# LM2596.net
KiCad netlist of a schematic drawn in Altium Designer
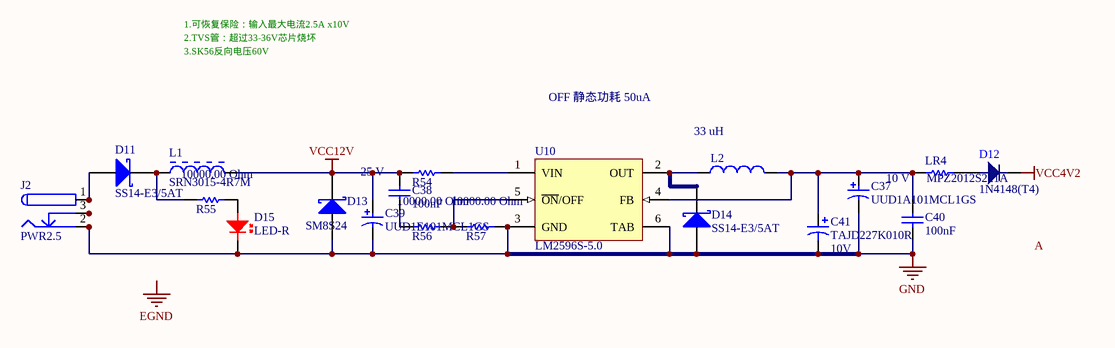
[diagram p0: LM2596.SchDoc]

(export (version "E")
  (design (tool "Eeschema 10.0.6"))
  (components
    (comp (ref "C37")
      (value "UUD1A101MCL1GS")
      (footprint "NIC-CAPA2-6.3X5.8_V")
      (fields (field (name "RATED VOLTAGE") "10 V") (field (name "MANUFACTURER") "Nichicon"))
      (libsource (lib "Altium Content Vault") (part "CMP-0687-00054-1"))
    )
    (comp (ref "C38")
      (value "100nF")
      (footprint "CAPC0805(2012)100_L")
      (description "CAP 100nF 50V ±5% 0805 (2012 Metric) Thickness 1mm SMD")
      (fields (field (name "TOLERANCE") "±5%") (field (name "Comment") "CAP 100nF 50V 0805(2012)"))
      (libsource (lib "Altium Content Vault") (part "CMP-1036-04418-1"))
    )
    (comp (ref "C39")
      (value "UUD1E101MCL1GS")
      (footprint "NIC-CAPA2-6.3X7.7_V")
      (fields (field (name "RATED VOLTAGE") "25 V") (field (name "MANUFACTURER") "Nichicon"))
      (libsource (lib "Altium Content Vault") (part "CMP-0687-00063-1"))
    )
    (comp (ref "C40")
      (value "100nF")
      (footprint "CAPC0805(2012)100_L")
      (description "CAP 100nF 50V ±5% 0805 (2012 Metric) Thickness 1mm SMD")
      (fields (field (name "TOLERANCE") "±5%") (field (name "Comment") "CAP 100nF 50V 0805(2012)"))
      (libsource (lib "Altium Content Vault") (part "CMP-1036-04418-1"))
    )
    (comp (ref "C41")
      (value "TAJD227K010R")
      (footprint "AVX-CAPC7343_V")
      (description "Capacitor, Tantalum, 220uF 10% 10V MCCT-D (7343-31)")
      (fields
        (field (name "MANUFACTURER") "AVX")
        (field (name "TOLERANCE") "10%")
        (field (name "RATED VOLTAGE") "10V")
      )
      (libsource (lib "Altium Content Vault") (part "CMP-0279-00002-1"))
    )
    (comp (ref "D11")
      (value "SS14-E3/5AT")
      (footprint "VISH-DO-214AC-2_V")
      (fields (field (name "MANUFACTURER") "Vishay Semiconductor"))
      (libsource (lib "Altium Content Vault") (part "VISH-DSKY_A1K2-2"))
    )
    (comp (ref "D12")
      (value "1N4148(T4)")
      (footprint "SOD-123")
      (description "高速开关二极管")
      (libsource (lib "mylib") (part "1N4148"))
    )
    (comp (ref "D13")
      (value "SM8S24")
      (footprint "Miscellaneous Devices:DIODE_SMC")
      (description "TVS")
      (libsource (lib "IR Rectifier - Schottky") (part "30BQ040"))
    )
    (comp (ref "D14")
      (value "SS14-E3/5AT")
      (footprint "VISH-DO-214AC-2_V")
      (fields (field (name "MANUFACTURER") "Vishay Semiconductor"))
      (libsource (lib "Altium Content Vault") (part "VISH-DSKY_A1K2-2"))
    )
    (comp (ref "D15")
      (value "LED-R")
      (footprint "DIO-LIG")
      (description "红色LED")
      (libsource (lib "mylib") (part "LED-RED"))
    )
    (comp (ref "J2")
      (value "PWR2.5")
      (footprint "KLD-0202")
      (description "Low Voltage Power Supply Connector")
      (fields (field (name "PUBLISHER") "Altium Limited"))
      (libsource (lib "Miscellaneous Connectors") (part "PWR2.5"))
    )
    (comp (ref "L1")
      (value "SRN3015-4R7M")
      (footprint "BOUR-SRN3015-2_V")
      (fields (field (name "MANUFACTURER") "Bourns"))
      (libsource (lib "Altium Content Vault") (part "BOUR-IND-2A"))
    )
    (comp (ref "L2")
      (value "SLF7045T-330M1R1-H")
      (footprint "INDP5050X28N")
      (description "固定电感器 SMD Power Inductor")
      (fields
        (field (name "MANUFACTURER") "TDK")
        (field (name "INDUCTANCE") "33 uH")
        (field (name "TOLERANCE") "20 %")
      )
      (libsource (lib "Miscellaneous Devices") (part "Inductor"))
    )
    (comp (ref "LR4")
      (value "MPZ2012S221A")
      (footprint "2012[0805]")
      (description "电磁干扰滤波珠子、扼流圈和阵列 Ferrite Chip Beads")
      (fields (field (name "MANUFACTURER") "TDK"))
      (libsource (lib "Miscellaneous Devices") (part "Res Semi"))
    )
    (comp (ref "R54")
      (value "2R 1% 0805(2012)")
      (footprint "RESC0805(2012)_L")
      (description "2R 0.125W 1% 0805 (2012 Metric)  SMD")
      (fields (field (name "TOLERANCE") "1 %") (field (name "POWER") "0.125 W"))
      (libsource (lib "Altium Content Vault") (part "RES"))
    )
    (comp (ref "R55")
      (value "10000.00 Ohm")
      (footprint "RESC0805(2012)_M")
      (description "10K 0.125W 1% 0805 (2012 Metric)  SMD")
      (fields (field (name "TOLERANCE") "1 %") (field (name "POWER") "0.125 W"))
      (libsource (lib "Altium Content Vault") (part "CMP-1013-00623-1"))
    )
    (comp (ref "R56")
      (value "10000.00 Ohm")
      (footprint "RESC0805(2012)_M")
      (description "10K 0.125W 1% 0805 (2012 Metric)  SMD")
      (fields (field (name "TOLERANCE") "1 %") (field (name "POWER") "0.125 W"))
      (libsource (lib "Altium Content Vault") (part "CMP-1013-00623-1"))
    )
    (comp (ref "R57")
      (value "10000.00 Ohm")
      (footprint "RESC0805(2012)_M")
      (description "10K 0.125W 1% 0805 (2012 Metric)  SMD")
      (fields (field (name "TOLERANCE") "1 %") (field (name "POWER") "0.125 W"))
      (libsource (lib "Altium Content Vault") (part "CMP-1013-00623-1"))
    )
    (comp (ref "U10")
      (value "LM2596S-5.0")
      (footprint "TS5B_N")
      (description "SIMPLE SWITCHER?Power Converter 150 KHz 3A Step-Down Voltage Regulator, 5-pin TO-263")
      (fields (field (name "MANUFACTURER") "National Semiconductor"))
      (libsource (lib "National Semiconductor Switcher") (part "LM2596S-5.0"))
    )
  )
  (nets
    (net (code "3") (name "GND") (class "Default")
      (node (ref "C37") (pin "2") (pinfunction "2_2") (pintype "passive"))
      (node (ref "C39") (pin "2") (pinfunction "2_2") (pintype "passive"))
      (node (ref "C40") (pin "1") (pinfunction "1_1") (pintype "passive"))
      (node (ref "C41") (pin "2") (pinfunction "2_2") (pintype "passive"))
      (node (ref "D13") (pin "1") (pinfunction "A_1") (pintype "passive"))
      (node (ref "D14") (pin "1") (pinfunction "A_1") (pintype "passive"))
      (node (ref "D15") (pin "2") (pintype "passive"))
      (node (ref "J2") (pin "2") (pinfunction "2_2") (pintype "power_in"))
      (node (ref "J2") (pin "2A") (pinfunction "2A_2A") (pintype "power_in"))
      (node (ref "J2") (pin "2B") (pinfunction "2B_2B") (pintype "power_in"))
      (node (ref "R57") (pin "2") (pinfunction "2_2") (pintype "passive"))
      (node (ref "U10") (pin "3") (pinfunction "GND_3") (pintype "power_in"))
      (node (ref "U10") (pin "6") (pinfunction "TAB_6") (pintype "power_in"))
    )
    (net (code "4") (name "Net-(C38-Pad1)") (class "Default")
      (node (ref "C38") (pin "1") (pinfunction "1_1") (pintype "passive"))
      (node (ref "R56") (pin "1") (pinfunction "1_1") (pintype "passive"))
    )
    (net (code "5") (name "Net-(D11-A)") (class "Default")
      (node (ref "D11") (pin "1") (pinfunction "A_1") (pintype "passive"))
      (node (ref "J2") (pin "1") (pinfunction "1_1") (pintype "power_in"))
      (node (ref "J2") (pin "1A") (pinfunction "1A_1A") (pintype "power_in"))
      (node (ref "J2") (pin "1B") (pinfunction "1B_1B") (pintype "power_in"))
    )
    (net (code "6") (name "Net-(D11-K)") (class "Default")
      (node (ref "D11") (pin "2") (pinfunction "K_2") (pintype "passive"))
      (node (ref "L1") (pin "1") (pinfunction "1_1") (pintype "passive"))
      (node (ref "R55") (pin "1") (pinfunction "1_1") (pintype "passive"))
    )
    (net (code "7") (name "Net-(D12-Pad1)") (class "Default")
      (node (ref "D12") (pin "1") (pintype "passive"))
      (node (ref "LR4") (pin "2") (pinfunction "2_2") (pintype "passive"))
    )
    (net (code "8") (name "Net-(D14-K)") (class "Default")
      (node (ref "D14") (pin "2") (pinfunction "K_2") (pintype "passive"))
      (node (ref "L2") (pin "1") (pinfunction "1_1") (pintype "passive"))
      (node (ref "U10") (pin "2") (pinfunction "OUT_2") (pintype "power_in"))
    )
    (net (code "9") (name "Net-(D15-Pad1)") (class "Default")
      (node (ref "D15") (pin "1") (pintype "passive"))
      (node (ref "R55") (pin "2") (pinfunction "2_2") (pintype "passive"))
    )
    (net (code "10") (name "Net-(J2-Pad3)") (class "Default")
      (node (ref "J2") (pin "3") (pinfunction "3_3") (pintype "power_in"))
      (node (ref "J2") (pin "3A") (pinfunction "3A_3A") (pintype "power_in"))
      (node (ref "J2") (pin "3B") (pinfunction "3B_3B") (pintype "power_in"))
    )
    (net (code "11") (name "Net-(U10-FB)") (class "Default")
      (node (ref "C37") (pin "1") (pinfunction "1_1") (pintype "passive"))
      (node (ref "C40") (pin "2") (pinfunction "2_2") (pintype "passive"))
      (node (ref "C41") (pin "1") (pinfunction "1_1") (pintype "passive"))
      (node (ref "L2") (pin "2") (pinfunction "2_2") (pintype "passive"))
      (node (ref "LR4") (pin "1") (pinfunction "1_1") (pintype "passive"))
      (node (ref "U10") (pin "4") (pinfunction "FB_4") (pintype "input"))
    )
    (net (code "12") (name "Net-(U10-VIN)") (class "Default")
      (node (ref "R54") (pin "2") (pinfunction "2_2") (pintype "passive"))
      (node (ref "U10") (pin "1") (pinfunction "VIN_1") (pintype "power_in"))
    )
    (net (code "13") (name "Net-(U10-~{ON}{slash}OFF)") (class "Default")
      (node (ref "R56") (pin "2") (pinfunction "2_2") (pintype "passive"))
      (node (ref "R57") (pin "1") (pinfunction "1_1") (pintype "passive"))
      (node (ref "U10") (pin "5") (pinfunction "~{ON}/OFF_5") (pintype "input"))
    )
    (net (code "14") (name "VCC4V2") (class "Default") (node (ref "D12") (pin "2") (pintype "passive")))
    (net (code "15") (name "VCC12V") (class "Default")
      (node (ref "C38") (pin "2") (pinfunction "2_2") (pintype "passive"))
      (node (ref "C39") (pin "1") (pinfunction "1_1") (pintype "passive"))
      (node (ref "D13") (pin "2") (pinfunction "K_2") (pintype "passive"))
      (node (ref "L1") (pin "2") (pinfunction "2_2") (pintype "passive"))
      (node (ref "R54") (pin "1") (pinfunction "1_1") (pintype "passive"))
    )
  )
)
